# Smoke-purifier-Mini.net
KiCad netlist of a schematic drawn in EasyEDA Pro
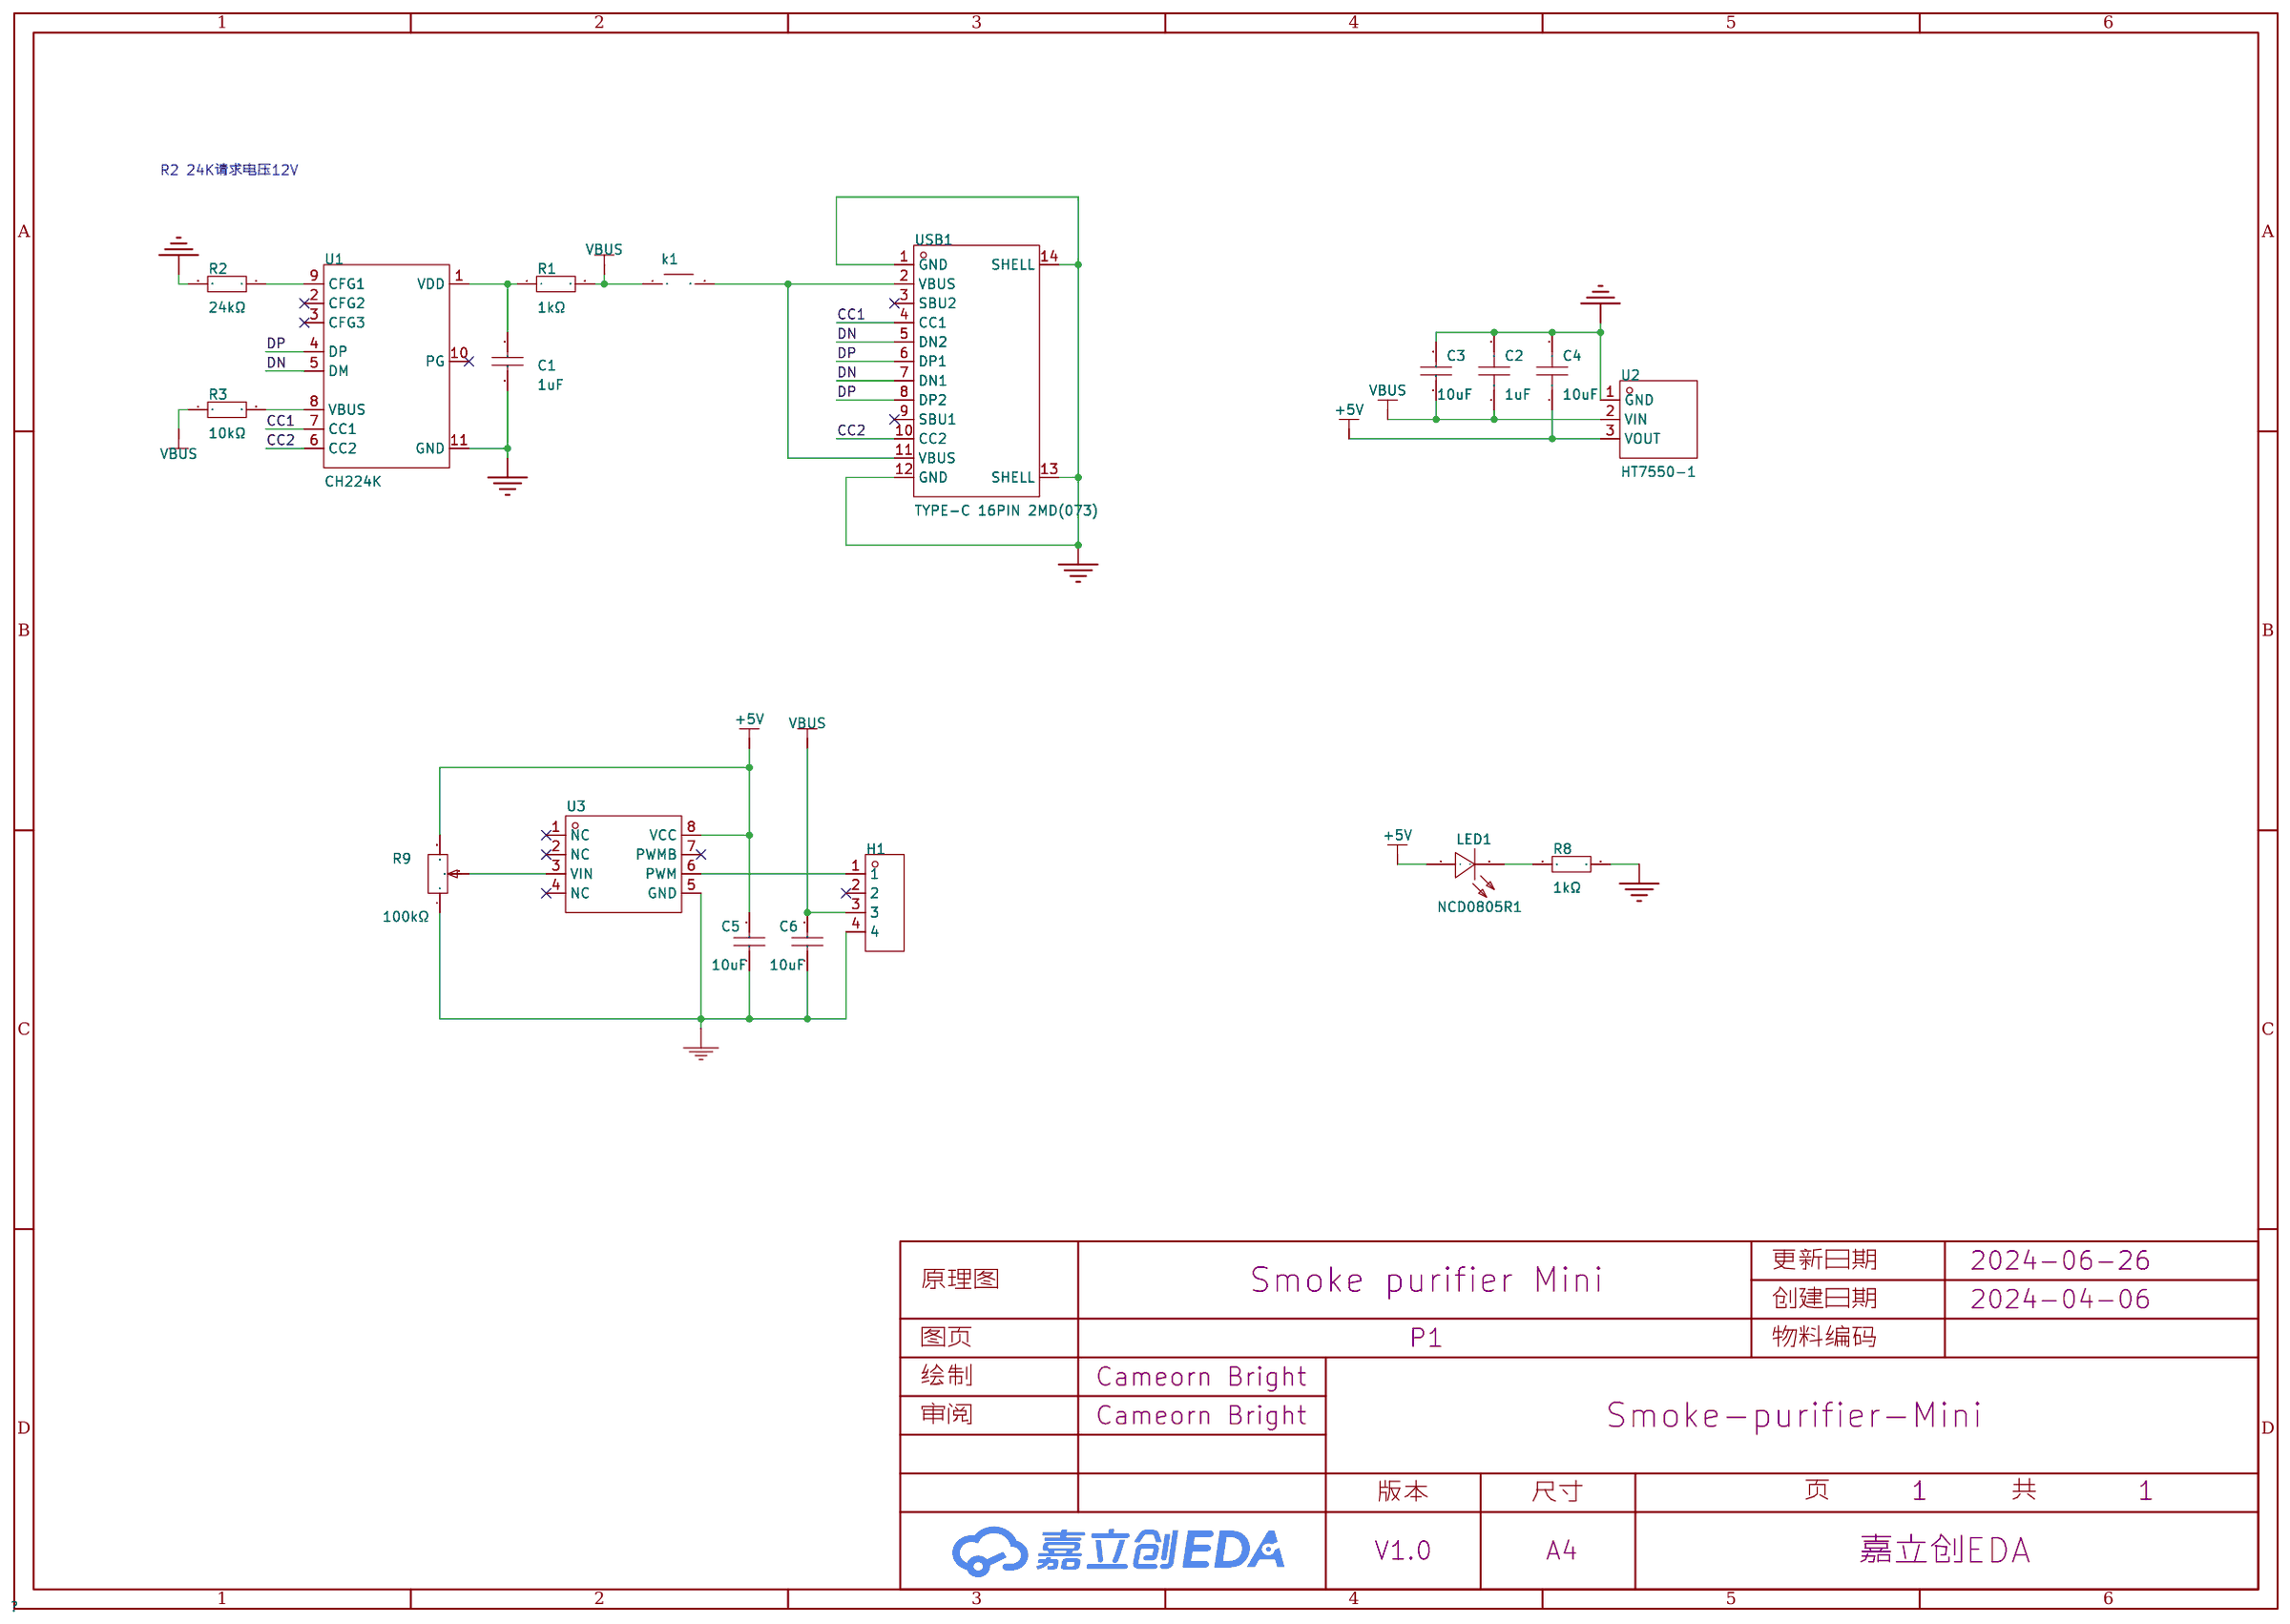
[diagram p0: schematic sheet]

(export (version "E")
  (design (tool "Eeschema 10.0.6"))
  (components
    (comp (ref "C1")
      (value "1uF")
      (footprint "easyedapro:C0603")
      (description "容值:1uF;精度:±10%;额定电压:50V;材质(温度系数):X5R;")
      (fields
        (field (name "Manufacturer Part") "CL10A105KB8NNNC")
        (field (name "Manufacturer") "SAMSUNG(三星)")
      )
      (libsource (lib "easyedapro") (part "CL10A105KB8NNNC"))
    )
    (comp (ref "C2")
      (value "1uF")
      (footprint "easyedapro:C0805")
      (description "容值:10uF;精度:±10%;额定电压:50V;材质(温度系数):X5R;")
      (fields
        (field (name "Manufacturer Part") "GRM21BR61H106KE43L")
        (field (name "Manufacturer") "muRata(村田)")
      )
      (libsource (lib "easyedapro") (part "GRM21BR61H106KE43L"))
    )
    (comp (ref "C3")
      (value "10uF")
      (footprint "easyedapro:C0805")
      (description "容值:1uF;精度:±10%;额定电压:50V;材质(温度系数):X7R;")
      (fields
        (field (name "Manufacturer Part") "CL21B105KBFNNNE")
        (field (name "Manufacturer") "SAMSUNG(三星)")
      )
      (libsource (lib "easyedapro") (part "CL21B105KBFNNNE"))
    )
    (comp (ref "C4")
      (value "10uF")
      (footprint "easyedapro:C0805")
      (description "容值:10uF;精度:±10%;额定电压:50V;材质(温度系数):X5R;")
      (fields
        (field (name "Manufacturer Part") "GRM21BR61H106KE43L")
        (field (name "Manufacturer") "muRata(村田)")
      )
      (libsource (lib "easyedapro") (part "GRM21BR61H106KE43L"))
    )
    (comp (ref "C5")
      (value "10uF")
      (fields
        (field (name "Manufacturer Part") "GRM188R6YA106MA73D")
        (field (name "Manufacturer") "muRata(村田)")
      )
      (libsource (lib "easyedapro") (part "cl10a106mo8nqnc"))
    )
    (comp (ref "C6")
      (value "10uF")
      (fields
        (field (name "Manufacturer Part") "GRM188R6YA106MA73D")
        (field (name "Manufacturer") "muRata(村田)")
      )
      (libsource (lib "easyedapro") (part "cl10a106mo8nqnc"))
    )
    (comp (ref "H1")
      (value "~")
      (footprint "easyedapro:HDR-TH_4P-P2.54-V-F")
      (libsource (lib "easyedapro") (part "2.54-1*4P母"))
    )
    (comp (ref "k1")
      (value "~")
      (footprint "easyedapro:Key_mini")
      (libsource (lib "easyedapro") (part "key1"))
    )
    (comp (ref "LED1")
      (value "NCD0805R1")
      (footprint "easyedapro:LED0805-R-RD")
      (fields (field (name "Manufacturer") "国星光电"))
      (libsource (lib "easyedapro") (part "FC-2012HRK-620D"))
    )
    (comp (ref "R1")
      (value "1kΩ")
      (footprint "easyedapro:R0603")
      (description "电阻类型:厚膜电阻;阻值:1kΩ;精度:±1%;功率:100mW;最大工作电压:75V;温度系数:±100ppm/°C;")
      (fields (field (name "Manufacturer Part") "RC0603FR-071KL") (field (name "Manufacturer") "YAGEO(国巨)"))
      (libsource (lib "easyedapro") (part "RC0603FR-071KL"))
    )
    (comp (ref "R2")
      (value "24kΩ")
      (footprint "easyedapro:R0603")
      (description "电阻类型:厚膜电阻;阻值:24kΩ;精度:±1%;功率:100mW;最大工作电压:75V;温度系数:±100ppm/°C;")
      (fields
        (field (name "Manufacturer Part") "0603WAF2402T5E")
        (field (name "Manufacturer") "UNI-ROYAL(厚声)")
      )
      (libsource (lib "easyedapro") (part "0603WAF2402T5E"))
    )
    (comp (ref "R3")
      (value "10kΩ")
      (footprint "easyedapro:R0603")
      (description "电阻类型:厚膜电阻;阻值:10kΩ;精度:±1%;功率:100mW;最大工作电压:75V;温度系数:±100ppm/°C;")
      (fields
        (field (name "Manufacturer Part") "0603WAF1002T5E")
        (field (name "Manufacturer") "UNI-ROYAL(厚声)")
      )
      (libsource (lib "easyedapro") (part "0603WAF1002T5E"))
    )
    (comp (ref "R8")
      (value "1kΩ")
      (footprint "easyedapro:R0603")
      (description "电阻类型:厚膜电阻;阻值:1kΩ;精度:±1%;功率:100mW;最大工作电压:75V;温度系数:±100ppm/°C;")
      (fields (field (name "Manufacturer Part") "RC0603FR-071KL") (field (name "Manufacturer") "YAGEO(国巨)"))
      (libsource (lib "easyedapro") (part "RC0603FR-071KL"))
    )
    (comp (ref "R9")
      (value "100kΩ")
      (footprint "easyedapro:RES-ADJ-TH_3296W")
      (description "阻值:100kΩ;精度:±10%;功率:500mW;温度系数:±100ppm/°C;")
      (fields (field (name "Manufacturer Part") "3296W-1-104LF") (field (name "Manufacturer") "BOURNS"))
      (libsource (lib "easyedapro") (part "3296W-1-104LF"))
    )
    (comp (ref "U1")
      (value "CH224K")
      (footprint "easyedapro:ESSOP-10_L4.9-W3.9-P1.0-LS6.0-TL-EP")
      (description "应用功能:USB充电芯片;")
      (fields (field (name "Manufacturer") "WCH(南京沁恒)"))
      (libsource (lib "easyedapro") (part "CH224K"))
    )
    (comp (ref "U2")
      (value "HT7550-1")
      (footprint "easyedapro:SOT-89_L4.5-W2.5-P1.50-LS4.2-BR")
      (description "输出类型:固定;最大输入电压:30V;输出电压:5V;最大输出电流:100mA;电源纹波抑制比(PSRR):-;输出极性:正极;")
      (fields (field (name "Manufacturer") "UMW(友台半导体)"))
      (libsource (lib "easyedapro") (part "HT7550-1_C347189"))
    )
    (comp (ref "U3")
      (value "GP9101-F20K-L2H1-SW")
      (footprint "easyedapro:SOP-8_L5.0-W3.9-P1.27-LS6.0-BL")
      (description "GP9101 0-VCC转PWM 20KHz L2H1")
      (fields (field (name "Manufacturer") "Guestgood(客益)"))
      (libsource (lib "easyedapro") (part "GP9101-F20K-L2H1-SW"))
    )
    (comp (ref "USB1")
      (value "TYPE-C 16PIN 2MD(073)")
      (footprint "easyedapro:USB-C-SMD_TYPE-C-6PIN-2MD-073")
      (description "连接器类型:Type-C;标准:-;公母:母;端口数量:1;触点数量:16P;安装方式:卧贴;额定电流 - 电源:5A;工作温度范围:-25°C~+85°C;")
      (fields (field (name "Manufacturer") "SHOU HAN(首韩)"))
      (libsource (lib "easyedapro") (part "TYPE-C 16PIN 2MD(073)"))
    )
  )
  (nets
    (net (code "1") (name "+5V") (class "Default")
      (node (ref "C4") (pin "1") (pinfunction "1_1") (pintype "unspecified"))
      (node (ref "C5") (pin "2") (pinfunction "2_2") (pintype "input"))
      (node (ref "LED1") (pin "1") (pinfunction "+_1") (pintype "unspecified"))
      (node (ref "R9") (pin "3") (pinfunction "3_3") (pintype "input"))
      (node (ref "U2") (pin "3") (pinfunction "VOUT_3") (pintype "unspecified"))
      (node (ref "U3") (pin "8") (pinfunction "VCC_8") (pintype "input"))
    )
    (net (code "2") (name "/CC1") (class "Default")
      (node (ref "U1") (pin "7") (pinfunction "CC1_7") (pintype "unspecified"))
      (node (ref "USB1") (pin "4") (pinfunction "CC1_4") (pintype "unspecified"))
    )
    (net (code "3") (name "/CC2") (class "Default")
      (node (ref "U1") (pin "6") (pinfunction "CC2_6") (pintype "unspecified"))
      (node (ref "USB1") (pin "10") (pinfunction "CC2_10") (pintype "unspecified"))
    )
    (net (code "4") (name "/DN") (class "Default")
      (node (ref "U1") (pin "5") (pinfunction "DM_5") (pintype "unspecified"))
      (node (ref "USB1") (pin "5") (pinfunction "DN2_5") (pintype "unspecified"))
      (node (ref "USB1") (pin "7") (pinfunction "DN1_7") (pintype "unspecified"))
    )
    (net (code "5") (name "/DP") (class "Default")
      (node (ref "U1") (pin "4") (pinfunction "DP_4") (pintype "unspecified"))
      (node (ref "USB1") (pin "6") (pinfunction "DP1_6") (pintype "unspecified"))
      (node (ref "USB1") (pin "8") (pinfunction "DP2_8") (pintype "unspecified"))
    )
    (net (code "6") (name "GND") (class "Default")
      (node (ref "C1") (pin "1") (pinfunction "1_1") (pintype "input"))
      (node (ref "C2") (pin "2") (pinfunction "2_2") (pintype "unspecified"))
      (node (ref "C3") (pin "2") (pinfunction "2_2") (pintype "input"))
      (node (ref "C4") (pin "2") (pinfunction "2_2") (pintype "unspecified"))
      (node (ref "C5") (pin "1") (pinfunction "1_1") (pintype "input"))
      (node (ref "C6") (pin "1") (pinfunction "1_1") (pintype "input"))
      (node (ref "H1") (pin "4") (pinfunction "4_4") (pintype "unspecified"))
      (node (ref "R2") (pin "2") (pinfunction "2_2") (pintype "input"))
      (node (ref "R8") (pin "2") (pinfunction "2_2") (pintype "input"))
      (node (ref "R9") (pin "1") (pinfunction "1_1") (pintype "input"))
      (node (ref "U1") (pin "11") (pinfunction "GND_11") (pintype "unspecified"))
      (node (ref "U2") (pin "1") (pinfunction "GND_1") (pintype "unspecified"))
      (node (ref "U3") (pin "5") (pinfunction "GND_5") (pintype "input"))
      (node (ref "USB1") (pin "1") (pinfunction "GND_1") (pintype "unspecified"))
      (node (ref "USB1") (pin "12") (pinfunction "GND_12") (pintype "unspecified"))
      (node (ref "USB1") (pin "13") (pinfunction "SHELL_13") (pintype "unspecified"))
      (node (ref "USB1") (pin "14") (pinfunction "SHELL_14") (pintype "unspecified"))
    )
    (net (code "7") (name "Net-(LED1--)") (class "Default")
      (node (ref "LED1") (pin "2") (pinfunction "-_2") (pintype "unspecified"))
      (node (ref "R8") (pin "1") (pinfunction "1_1") (pintype "input"))
    )
    (net (code "8") (name "Net-(U1-CFG1)") (class "Default")
      (node (ref "R2") (pin "1") (pinfunction "1_1") (pintype "input"))
      (node (ref "U1") (pin "9") (pinfunction "CFG1_9") (pintype "unspecified"))
    )
    (net (code "9") (name "Net-(U1-VBUS)") (class "Default")
      (node (ref "R3") (pin "2") (pinfunction "2_2") (pintype "input"))
      (node (ref "U1") (pin "8") (pinfunction "VBUS_8") (pintype "unspecified"))
    )
    (net (code "10") (name "Net-(U1-VDD)") (class "Default")
      (node (ref "C1") (pin "2") (pinfunction "2_2") (pintype "input"))
      (node (ref "R1") (pin "1") (pinfunction "1_1") (pintype "input"))
      (node (ref "U1") (pin "1") (pinfunction "VDD_1") (pintype "unspecified"))
    )
    (net (code "11") (name "Net-(U3-PWM)") (class "Default")
      (node (ref "H1") (pin "1") (pinfunction "1_1") (pintype "unspecified"))
      (node (ref "U3") (pin "6") (pinfunction "PWM_6") (pintype "input"))
    )
    (net (code "12") (name "Net-(U3-VIN)") (class "Default")
      (node (ref "R9") (pin "2") (pinfunction "2_2") (pintype "input"))
      (node (ref "U3") (pin "3") (pinfunction "VIN_3") (pintype "input"))
    )
    (net (code "13") (name "Net-(USB1-VBUS-Pad11)") (class "Default")
      (node (ref "USB1") (pin "11") (pinfunction "VBUS_11") (pintype "unspecified"))
      (node (ref "USB1") (pin "2") (pinfunction "VBUS_2") (pintype "unspecified"))
      (node (ref "k1") (pin "2") (pinfunction "2_2") (pintype "input"))
    )
    (net (code "14") (name "VBUS") (class "Default")
      (node (ref "C2") (pin "1") (pinfunction "1_1") (pintype "unspecified"))
      (node (ref "C3") (pin "1") (pinfunction "1_1") (pintype "input"))
      (node (ref "C6") (pin "2") (pinfunction "2_2") (pintype "input"))
      (node (ref "H1") (pin "3") (pinfunction "3_3") (pintype "unspecified"))
      (node (ref "R1") (pin "2") (pinfunction "2_2") (pintype "input"))
      (node (ref "R3") (pin "1") (pinfunction "1_1") (pintype "input"))
      (node (ref "U2") (pin "2") (pinfunction "VIN_2") (pintype "unspecified"))
      (node (ref "k1") (pin "1") (pinfunction "1_1") (pintype "input"))
    )
    (net (code "15") (name "unconnected-(H1-Pad2)") (class "Default")
      (node (ref "H1") (pin "2") (pinfunction "2_2") (pintype "unspecified+no_connect"))
    )
    (net (code "16") (name "unconnected-(U1-CFG2-Pad2)") (class "Default")
      (node (ref "U1") (pin "2") (pinfunction "CFG2_2") (pintype "unspecified+no_connect"))
    )
    (net (code "17") (name "unconnected-(U1-CFG3-Pad3)") (class "Default")
      (node (ref "U1") (pin "3") (pinfunction "CFG3_3") (pintype "unspecified+no_connect"))
    )
    (net (code "18") (name "unconnected-(U1-PG-Pad10)") (class "Default")
      (node (ref "U1") (pin "10") (pinfunction "PG_10") (pintype "unspecified+no_connect"))
    )
    (net (code "19") (name "unconnected-(U3-NC-Pad1)") (class "Default")
      (node (ref "U3") (pin "1") (pinfunction "NC_1") (pintype "input+no_connect"))
    )
    (net (code "20") (name "unconnected-(U3-NC-Pad2)") (class "Default")
      (node (ref "U3") (pin "2") (pinfunction "NC_2") (pintype "input+no_connect"))
    )
    (net (code "21") (name "unconnected-(U3-NC-Pad4)") (class "Default")
      (node (ref "U3") (pin "4") (pinfunction "NC_4") (pintype "input+no_connect"))
    )
    (net (code "22") (name "unconnected-(U3-PWMB-Pad7)") (class "Default")
      (node (ref "U3") (pin "7") (pinfunction "PWMB_7") (pintype "input+no_connect"))
    )
    (net (code "23") (name "unconnected-(USB1-SBU1-Pad9)") (class "Default")
      (node (ref "USB1") (pin "9") (pinfunction "SBU1_9") (pintype "unspecified+no_connect"))
    )
    (net (code "24") (name "unconnected-(USB1-SBU2-Pad3)") (class "Default")
      (node (ref "USB1") (pin "3") (pinfunction "SBU2_3") (pintype "unspecified+no_connect"))
    )
  )
)
